# lyre_v1_1.net
KiCad netlist of a schematic drawn in EAGLE
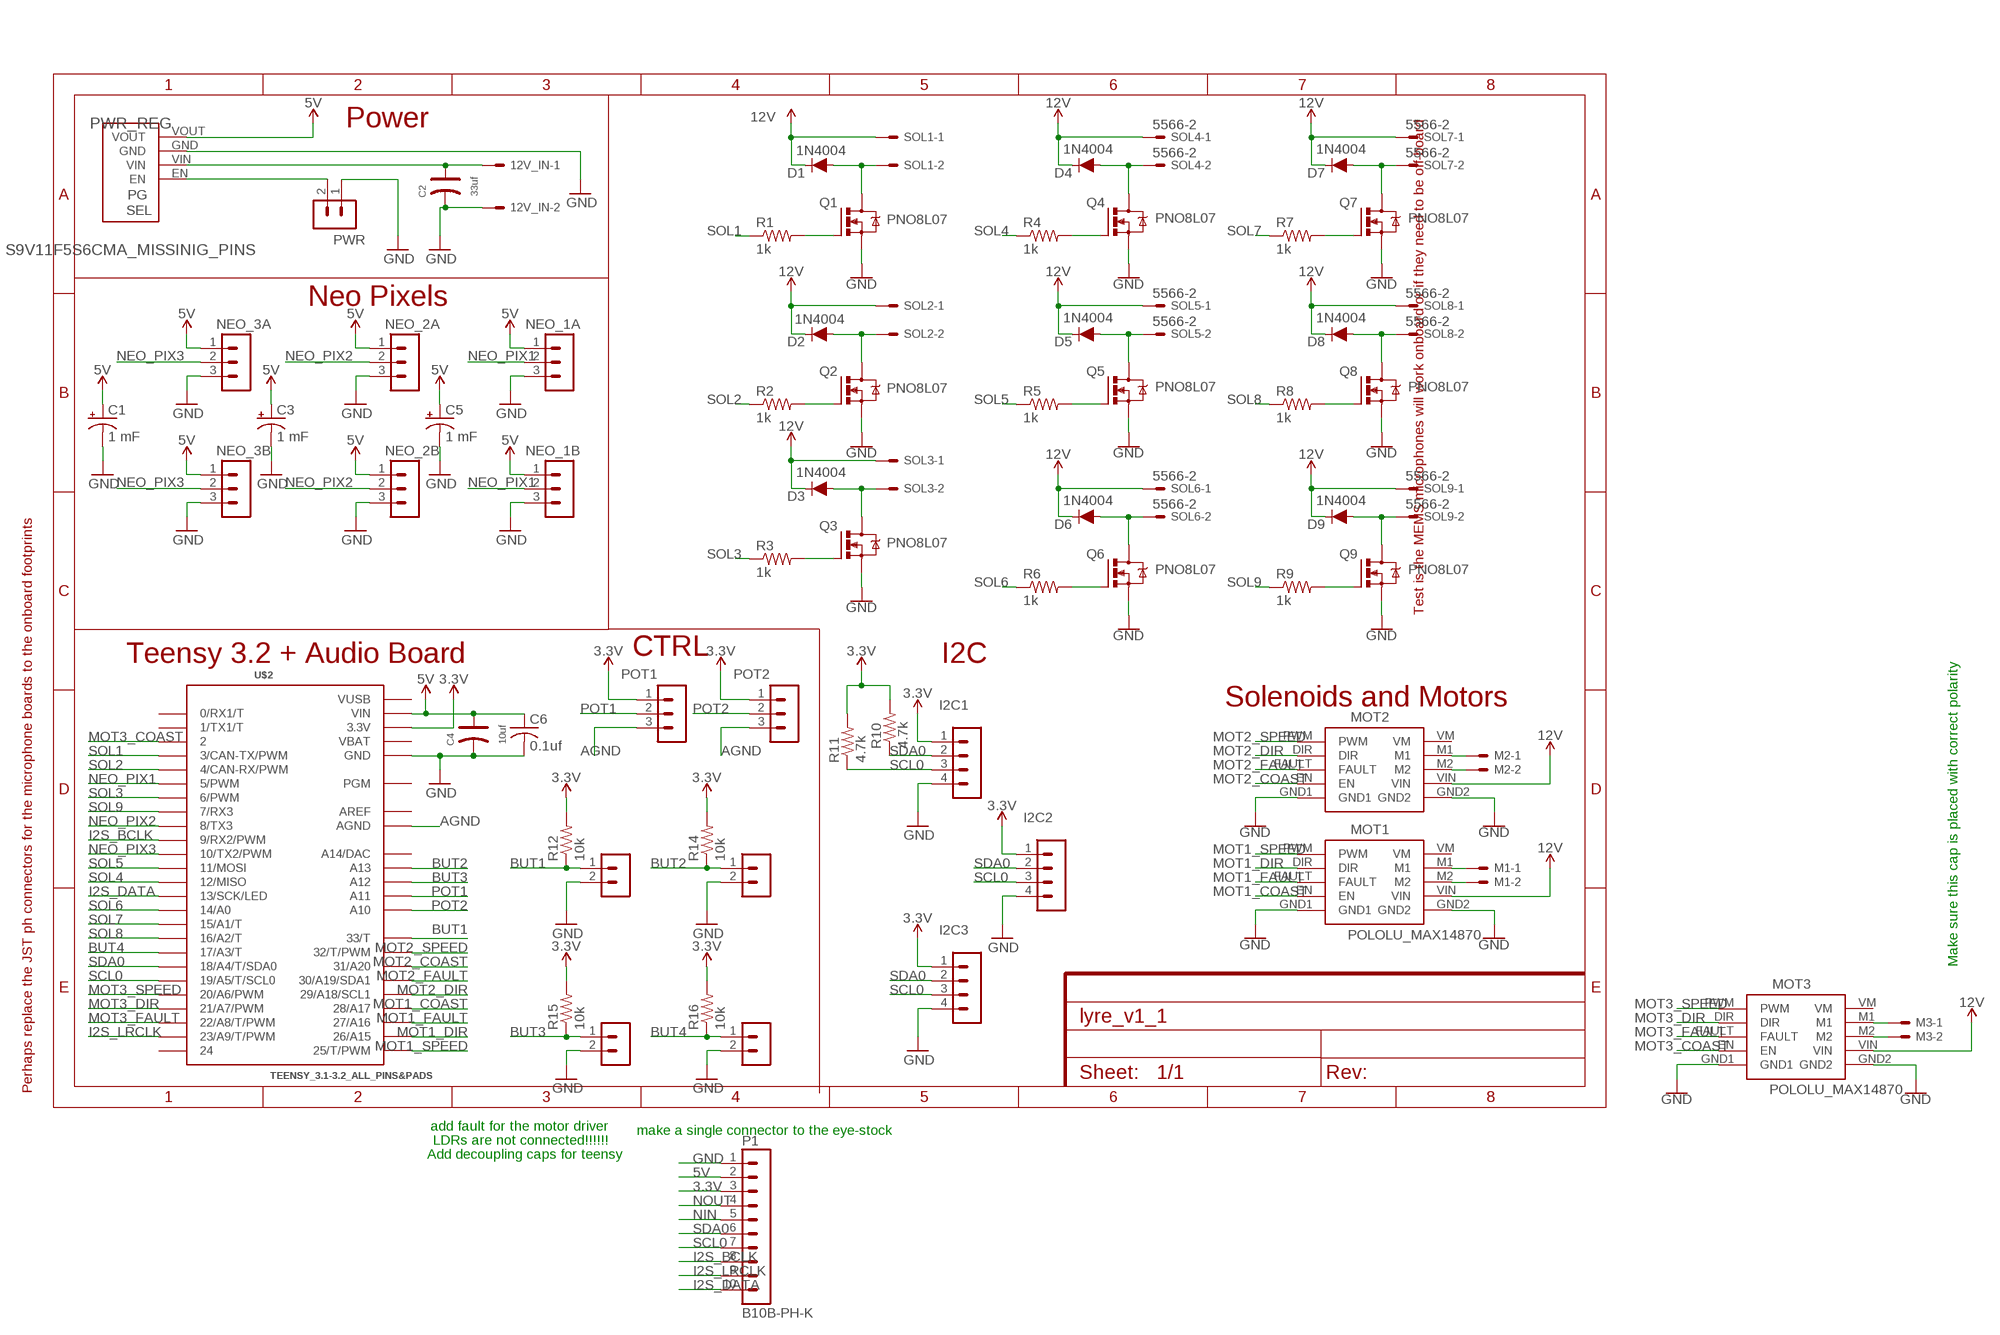
[diagram p0: schematic, sheet 1]

(export (version "E")
  (design (tool "Eeschema 10.0.6"))
  (components
    (comp (ref "12V_IN")
      (value "5566-2")
      (footprint "eagle-import:5566-2")
      (fields (field (name "MF") "MOLEX"))
      (libsource (lib "eagle-import") (part "5566-2"))
    )
    (comp (ref "BUT1")
      (value "B2B-PH-K")
      (footprint "eagle-import:B2B-PH-K")
      (libsource (lib "eagle-import") (part "B2B-PH-K"))
    )
    (comp (ref "BUT2")
      (value "B2B-PH-K")
      (footprint "eagle-import:B2B-PH-K")
      (libsource (lib "eagle-import") (part "B2B-PH-K"))
    )
    (comp (ref "BUT3")
      (value "B2B-PH-K")
      (footprint "eagle-import:B2B-PH-K")
      (libsource (lib "eagle-import") (part "B2B-PH-K"))
    )
    (comp (ref "BUT4")
      (value "B2B-PH-K")
      (footprint "eagle-import:B2B-PH-K")
      (libsource (lib "eagle-import") (part "B2B-PH-K"))
    )
    (comp (ref "C1")
      (value "1 mF")
      (footprint "eagle-import:UD-10X10_NICHICON")
      (libsource (lib "eagle-import") (part "CPOL-USUD-10X10"))
    )
    (comp (ref "C2")
      (value "33uf")
      (footprint "eagle-import:PC-D5.3MM")
      (fields (field (name "MPN") "KS 100uF/16V"))
      (libsource (lib "eagle-import") (part "DIP-ALUMINUM-47UF-16V(D5-H7MM)"))
    )
    (comp (ref "C3")
      (value "1 mF")
      (footprint "eagle-import:UD-10X10_NICHICON")
      (libsource (lib "eagle-import") (part "CPOL-USUD-10X10"))
    )
    (comp (ref "C4")
      (value "10uf")
      (footprint "eagle-import:PC-D5.3MM")
      (fields (field (name "MPN") "KS 100uF/16V"))
      (libsource (lib "eagle-import") (part "DIP-ALUMINUM-47UF-16V(D5-H7MM)"))
    )
    (comp (ref "C5")
      (value "1 mF")
      (footprint "eagle-import:UD-10X10_NICHICON")
      (libsource (lib "eagle-import") (part "CPOL-USUD-10X10"))
    )
    (comp (ref "C6")
      (value "0.1uf")
      (footprint "eagle-import:C2012")
      (libsource (lib "eagle-import") (part "C-USC2012"))
    )
    (comp (ref "D1")
      (value "1N4004")
      (footprint "eagle-import:DIOAD1138W86L465D235B")
      (libsource (lib "eagle-import") (part "1N4004"))
    )
    (comp (ref "D2")
      (value "1N4004")
      (footprint "eagle-import:DIOAD1138W86L465D235B")
      (libsource (lib "eagle-import") (part "1N4004"))
    )
    (comp (ref "D3")
      (value "1N4004")
      (footprint "eagle-import:DIOAD1138W86L465D235B")
      (libsource (lib "eagle-import") (part "1N4004"))
    )
    (comp (ref "D4")
      (value "1N4004")
      (footprint "eagle-import:DIOAD1138W86L465D235B")
      (libsource (lib "eagle-import") (part "1N4004"))
    )
    (comp (ref "D5")
      (value "1N4004")
      (footprint "eagle-import:DIOAD1138W86L465D235B")
      (libsource (lib "eagle-import") (part "1N4004"))
    )
    (comp (ref "D6")
      (value "1N4004")
      (footprint "eagle-import:DIOAD1138W86L465D235B")
      (libsource (lib "eagle-import") (part "1N4004"))
    )
    (comp (ref "D7")
      (value "1N4004")
      (footprint "eagle-import:DIOAD1138W86L465D235B")
      (libsource (lib "eagle-import") (part "1N4004"))
    )
    (comp (ref "D8")
      (value "1N4004")
      (footprint "eagle-import:DIOAD1138W86L465D235B")
      (libsource (lib "eagle-import") (part "1N4004"))
    )
    (comp (ref "D9")
      (value "1N4004")
      (footprint "eagle-import:DIOAD1138W86L465D235B")
      (libsource (lib "eagle-import") (part "1N4004"))
    )
    (comp (ref "I2C1")
      (value "B4B-PH-K")
      (footprint "eagle-import:B4B-PH-K")
      (libsource (lib "eagle-import") (part "B4B-PH-K"))
    )
    (comp (ref "I2C2")
      (value "B4B-PH-K")
      (footprint "eagle-import:B4B-PH-K")
      (libsource (lib "eagle-import") (part "B4B-PH-K"))
    )
    (comp (ref "I2C3")
      (value "B4B-PH-K")
      (footprint "eagle-import:B4B-PH-K")
      (libsource (lib "eagle-import") (part "B4B-PH-K"))
    )
    (comp (ref "M1")
      (value "5566-2")
      (footprint "eagle-import:5566-2")
      (fields (field (name "MF") "MOLEX"))
      (libsource (lib "eagle-import") (part "5566-2"))
    )
    (comp (ref "M2")
      (value "5566-2")
      (footprint "eagle-import:5566-2")
      (fields (field (name "MF") "MOLEX"))
      (libsource (lib "eagle-import") (part "5566-2"))
    )
    (comp (ref "M3")
      (value "5566-2")
      (footprint "eagle-import:5566-2")
      (fields (field (name "MF") "MOLEX"))
      (libsource (lib "eagle-import") (part "5566-2"))
    )
    (comp (ref "MOT1")
      (value "POLOLU_MAX14870")
      (footprint "eagle-import:POLOLU_MAX14870")
      (libsource (lib "eagle-import") (part "POLOLU_MAX14870"))
    )
    (comp (ref "MOT2")
      (value "POLOLU_MAX14870")
      (footprint "eagle-import:POLOLU_MAX14870")
      (libsource (lib "eagle-import") (part "POLOLU_MAX14870"))
    )
    (comp (ref "MOT3")
      (value "POLOLU_MAX14870")
      (footprint "eagle-import:POLOLU_MAX14870")
      (libsource (lib "eagle-import") (part "POLOLU_MAX14870"))
    )
    (comp (ref "NEO_1A")
      (value "B3B-PH-K")
      (footprint "eagle-import:B3B-PH-K")
      (libsource (lib "eagle-import") (part "B3B-PH-K"))
    )
    (comp (ref "NEO_1B")
      (value "B3B-PH-K")
      (footprint "eagle-import:B3B-PH-K")
      (libsource (lib "eagle-import") (part "B3B-PH-K"))
    )
    (comp (ref "NEO_2A")
      (value "B3B-PH-K")
      (footprint "eagle-import:B3B-PH-K")
      (libsource (lib "eagle-import") (part "B3B-PH-K"))
    )
    (comp (ref "NEO_2B")
      (value "B3B-PH-K")
      (footprint "eagle-import:B3B-PH-K")
      (libsource (lib "eagle-import") (part "B3B-PH-K"))
    )
    (comp (ref "NEO_3A")
      (value "B3B-PH-K")
      (footprint "eagle-import:B3B-PH-K")
      (libsource (lib "eagle-import") (part "B3B-PH-K"))
    )
    (comp (ref "NEO_3B")
      (value "B3B-PH-K")
      (footprint "eagle-import:B3B-PH-K")
      (libsource (lib "eagle-import") (part "B3B-PH-K"))
    )
    (comp (ref "P1")
      (value "B10B-PH-K")
      (footprint "eagle-import:B10B-PH-K")
      (libsource (lib "eagle-import") (part "B10B-PH-K"))
    )
    (comp (ref "POT1")
      (value "B3B-PH-K")
      (footprint "eagle-import:B3B-PH-K")
      (libsource (lib "eagle-import") (part "B3B-PH-K"))
    )
    (comp (ref "POT2")
      (value "B3B-PH-K")
      (footprint "eagle-import:B3B-PH-K")
      (libsource (lib "eagle-import") (part "B3B-PH-K"))
    )
    (comp (ref "PWR")
      (value "B2B-PH-K")
      (footprint "eagle-import:B2B-PH-K")
      (libsource (lib "eagle-import") (part "B2B-PH-K"))
    )
    (comp (ref "PWR_REG")
      (value "S9V11F5S6CMA_MISSINIG_PINS")
      (footprint "eagle-import:S9V11F3S5CMA_MISSING_PINS")
      (libsource (lib "eagle-import") (part "S9V11F5S6CMA_MISSINIG_PINS"))
    )
    (comp (ref "Q1")
      (value "PNO8L07")
      (footprint "eagle-import:TO220BV")
      (libsource (lib "eagle-import") (part "IRF540"))
    )
    (comp (ref "Q2")
      (value "PNO8L07")
      (footprint "eagle-import:TO220BV")
      (libsource (lib "eagle-import") (part "IRF540"))
    )
    (comp (ref "Q3")
      (value "PNO8L07")
      (footprint "eagle-import:TO220BV")
      (libsource (lib "eagle-import") (part "IRF540"))
    )
    (comp (ref "Q4")
      (value "PNO8L07")
      (footprint "eagle-import:TO220BV")
      (libsource (lib "eagle-import") (part "IRF540"))
    )
    (comp (ref "Q5")
      (value "PNO8L07")
      (footprint "eagle-import:TO220BV")
      (libsource (lib "eagle-import") (part "IRF540"))
    )
    (comp (ref "Q6")
      (value "PNO8L07")
      (footprint "eagle-import:TO220BV")
      (libsource (lib "eagle-import") (part "IRF540"))
    )
    (comp (ref "Q7")
      (value "PNO8L07")
      (footprint "eagle-import:TO220BV")
      (libsource (lib "eagle-import") (part "IRF540"))
    )
    (comp (ref "Q8")
      (value "PNO8L07")
      (footprint "eagle-import:TO220BV")
      (libsource (lib "eagle-import") (part "IRF540"))
    )
    (comp (ref "Q9")
      (value "PNO8L07")
      (footprint "eagle-import:TO220BV")
      (libsource (lib "eagle-import") (part "IRF540"))
    )
    (comp (ref "R1")
      (value "1k")
      (footprint "eagle-import:R0805")
      (libsource (lib "eagle-import") (part "R-US_R0805"))
    )
    (comp (ref "R2")
      (value "1k")
      (footprint "eagle-import:R0805")
      (libsource (lib "eagle-import") (part "R-US_R0805"))
    )
    (comp (ref "R3")
      (value "1k")
      (footprint "eagle-import:R0805")
      (libsource (lib "eagle-import") (part "R-US_R0805"))
    )
    (comp (ref "R4")
      (value "1k")
      (footprint "eagle-import:R0805")
      (libsource (lib "eagle-import") (part "R-US_R0805"))
    )
    (comp (ref "R5")
      (value "1k")
      (footprint "eagle-import:R0805")
      (libsource (lib "eagle-import") (part "R-US_R0805"))
    )
    (comp (ref "R6")
      (value "1k")
      (footprint "eagle-import:R0805")
      (libsource (lib "eagle-import") (part "R-US_R0805"))
    )
    (comp (ref "R7")
      (value "1k")
      (footprint "eagle-import:R0805")
      (libsource (lib "eagle-import") (part "R-US_R0805"))
    )
    (comp (ref "R8")
      (value "1k")
      (footprint "eagle-import:R0805")
      (libsource (lib "eagle-import") (part "R-US_R0805"))
    )
    (comp (ref "R9")
      (value "1k")
      (footprint "eagle-import:R0805")
      (libsource (lib "eagle-import") (part "R-US_R0805"))
    )
    (comp (ref "R10")
      (value "4.7k")
      (footprint "eagle-import:R0805")
      (libsource (lib "eagle-import") (part "R-US_R0805"))
    )
    (comp (ref "R11")
      (value "4.7k")
      (footprint "eagle-import:R0805")
      (libsource (lib "eagle-import") (part "R-US_R0805"))
    )
    (comp (ref "R12")
      (value "10k")
      (footprint "eagle-import:R0805")
      (libsource (lib "eagle-import") (part "R-US_R0805"))
    )
    (comp (ref "R14")
      (value "10k")
      (footprint "eagle-import:R0805")
      (libsource (lib "eagle-import") (part "R-US_R0805"))
    )
    (comp (ref "R15")
      (value "10k")
      (footprint "eagle-import:R0805")
      (libsource (lib "eagle-import") (part "R-US_R0805"))
    )
    (comp (ref "R16")
      (value "10k")
      (footprint "eagle-import:R0805")
      (libsource (lib "eagle-import") (part "R-US_R0805"))
    )
    (comp (ref "SOL1")
      (value "5566-2")
      (footprint "eagle-import:5566-2")
      (fields (field (name "MF") "MOLEX"))
      (libsource (lib "eagle-import") (part "5566-2"))
    )
    (comp (ref "SOL2")
      (value "5566-2")
      (footprint "eagle-import:5566-2")
      (fields (field (name "MF") "MOLEX"))
      (libsource (lib "eagle-import") (part "5566-2"))
    )
    (comp (ref "SOL3")
      (value "5566-2")
      (footprint "eagle-import:5566-2")
      (fields (field (name "MF") "MOLEX"))
      (libsource (lib "eagle-import") (part "5566-2"))
    )
    (comp (ref "SOL4")
      (value "5566-2")
      (footprint "eagle-import:5566-2")
      (fields (field (name "MF") "MOLEX"))
      (libsource (lib "eagle-import") (part "5566-2"))
    )
    (comp (ref "SOL5")
      (value "5566-2")
      (footprint "eagle-import:5566-2")
      (fields (field (name "MF") "MOLEX"))
      (libsource (lib "eagle-import") (part "5566-2"))
    )
    (comp (ref "SOL6")
      (value "5566-2")
      (footprint "eagle-import:5566-2")
      (fields (field (name "MF") "MOLEX"))
      (libsource (lib "eagle-import") (part "5566-2"))
    )
    (comp (ref "SOL7")
      (value "5566-2")
      (footprint "eagle-import:5566-2")
      (fields (field (name "MF") "MOLEX"))
      (libsource (lib "eagle-import") (part "5566-2"))
    )
    (comp (ref "SOL8")
      (value "5566-2")
      (footprint "eagle-import:5566-2")
      (fields (field (name "MF") "MOLEX"))
      (libsource (lib "eagle-import") (part "5566-2"))
    )
    (comp (ref "SOL9")
      (value "5566-2")
      (footprint "eagle-import:5566-2")
      (fields (field (name "MF") "MOLEX"))
      (libsource (lib "eagle-import") (part "5566-2"))
    )
    (comp (ref "U$2")
      (value "TEENSY_3.1-3.2_ALL_PINS&PADS")
      (footprint "eagle-import:TEENSY_3.0-3.2_ALL_PINS_&_PADS")
      (libsource (lib "eagle-import") (part "TEENSY_3.1-3.2_ALL_PINS&PADS"))
    )
  )
  (nets
    (net (code "1") (name "/AGND") (class "Default")
      (node (ref "POT1") (pin "3") (pinfunction "3_3") (pintype "passive"))
      (node (ref "POT2") (pin "3") (pinfunction "3_3") (pintype "passive"))
      (node (ref "U$2") (pin "AGND") (pinfunction "AGND_AGND") (pintype "power_in"))
    )
    (net (code "2") (name "/AREF") (class "Default")
      (node (ref "U$2") (pin "AREF") (pinfunction "AREF_AREF") (pintype "power_in"))
    )
    (net (code "3") (name "/BUT1") (class "Default")
      (node (ref "BUT1") (pin "1") (pinfunction "1_1") (pintype "passive"))
      (node (ref "R12") (pin "1") (pinfunction "1_1") (pintype "passive"))
      (node (ref "U$2") (pin "33") (pinfunction "33/T_33") (pintype "bidirectional"))
    )
    (net (code "4") (name "/BUT2") (class "Default")
      (node (ref "BUT2") (pin "1") (pinfunction "1_1") (pintype "passive"))
      (node (ref "R14") (pin "1") (pinfunction "1_1") (pintype "passive"))
      (node (ref "U$2") (pin "A13") (pinfunction "A13_A13") (pintype "bidirectional"))
    )
    (net (code "5") (name "/BUT3") (class "Default")
      (node (ref "BUT3") (pin "1") (pinfunction "1_1") (pintype "passive"))
      (node (ref "R15") (pin "1") (pinfunction "1_1") (pintype "passive"))
      (node (ref "U$2") (pin "A12") (pinfunction "A12_A12") (pintype "bidirectional"))
    )
    (net (code "6") (name "/BUT4") (class "Default")
      (node (ref "BUT4") (pin "1") (pinfunction "1_1") (pintype "passive"))
      (node (ref "R16") (pin "1") (pinfunction "1_1") (pintype "passive"))
      (node (ref "U$2") (pin "17/A3") (pinfunction "17/A3/T_17/A3") (pintype "bidirectional"))
    )
    (net (code "7") (name "/I2S_BCLK") (class "Default")
      (node (ref "P1") (pin "8") (pinfunction "8_8") (pintype "passive"))
      (node (ref "U$2") (pin "9") (pinfunction "9/RX2/PWM_9") (pintype "bidirectional"))
    )
    (net (code "8") (name "/I2S_DATA") (class "Default")
      (node (ref "P1") (pin "10") (pinfunction "10_10") (pintype "passive"))
      (node (ref "U$2") (pin "13") (pinfunction "13/SCK/LED_13") (pintype "bidirectional"))
    )
    (net (code "9") (name "/I2S_LRCLK") (class "Default")
      (node (ref "P1") (pin "9") (pinfunction "9_9") (pintype "passive"))
      (node (ref "U$2") (pin "23/A9") (pinfunction "23/A9/T/PWM_23/A9") (pintype "bidirectional"))
    )
    (net (code "10") (name "/MOT1_COAST") (class "Default")
      (node (ref "MOT1") (pin "EN") (pinfunction "EN_EN") (pintype "bidirectional"))
      (node (ref "U$2") (pin "28") (pinfunction "28/A17_28") (pintype "bidirectional"))
    )
    (net (code "11") (name "/MOT1_DIR") (class "Default")
      (node (ref "MOT1") (pin "DIR") (pinfunction "DIR_DIR") (pintype "bidirectional"))
      (node (ref "U$2") (pin "26") (pinfunction "26/A15_26") (pintype "bidirectional"))
    )
    (net (code "12") (name "/MOT1_FAULT") (class "Default")
      (node (ref "MOT1") (pin "FAULT") (pinfunction "FAULT_FAULT") (pintype "bidirectional"))
      (node (ref "U$2") (pin "27") (pinfunction "27/A16_27") (pintype "bidirectional"))
    )
    (net (code "13") (name "/MOT1_SPEED") (class "Default")
      (node (ref "MOT1") (pin "PWM") (pinfunction "PWM_PWM") (pintype "bidirectional"))
      (node (ref "U$2") (pin "25") (pinfunction "25/T/PWM_25") (pintype "bidirectional"))
    )
    (net (code "14") (name "/MOT2_COAST") (class "Default")
      (node (ref "MOT2") (pin "EN") (pinfunction "EN_EN") (pintype "bidirectional"))
      (node (ref "U$2") (pin "31") (pinfunction "31/A20_31") (pintype "bidirectional"))
    )
    (net (code "15") (name "/MOT2_DIR") (class "Default")
      (node (ref "MOT2") (pin "DIR") (pinfunction "DIR_DIR") (pintype "bidirectional"))
      (node (ref "U$2") (pin "29") (pinfunction "29/A18/SCL1_29") (pintype "bidirectional"))
    )
    (net (code "16") (name "/MOT2_FAULT") (class "Default")
      (node (ref "MOT2") (pin "FAULT") (pinfunction "FAULT_FAULT") (pintype "bidirectional"))
      (node (ref "U$2") (pin "30") (pinfunction "30/A19/SDA1_30") (pintype "bidirectional"))
    )
    (net (code "17") (name "/MOT2_SPEED") (class "Default")
      (node (ref "MOT2") (pin "PWM") (pinfunction "PWM_PWM") (pintype "bidirectional"))
      (node (ref "U$2") (pin "32") (pinfunction "32/T/PWM_32") (pintype "bidirectional"))
    )
    (net (code "18") (name "/MOT3_COAST") (class "Default")
      (node (ref "MOT3") (pin "EN") (pinfunction "EN_EN") (pintype "bidirectional"))
      (node (ref "U$2") (pin "2") (pinfunction "2_2") (pintype "bidirectional"))
    )
    (net (code "19") (name "/MOT3_DIR") (class "Default")
      (node (ref "MOT3") (pin "DIR") (pinfunction "DIR_DIR") (pintype "bidirectional"))
      (node (ref "U$2") (pin "21/A7") (pinfunction "21/A7/PWM_21/A7") (pintype "bidirectional"))
    )
    (net (code "20") (name "/MOT3_FAULT") (class "Default")
      (node (ref "MOT3") (pin "FAULT") (pinfunction "FAULT_FAULT") (pintype "bidirectional"))
      (node (ref "U$2") (pin "22/A8") (pinfunction "22/A8/T/PWM_22/A8") (pintype "bidirectional"))
    )
    (net (code "21") (name "/MOT3_SPEED") (class "Default")
      (node (ref "MOT3") (pin "PWM") (pinfunction "PWM_PWM") (pintype "bidirectional"))
      (node (ref "U$2") (pin "20/A6") (pinfunction "20/A6/PWM_20/A6") (pintype "bidirectional"))
    )
    (net (code "22") (name "/NEO_PIX1") (class "Default")
      (node (ref "NEO_1A") (pin "2") (pinfunction "2_2") (pintype "passive"))
      (node (ref "NEO_1B") (pin "2") (pinfunction "2_2") (pintype "passive"))
      (node (ref "U$2") (pin "5") (pinfunction "5/PWM_5") (pintype "bidirectional"))
    )
    (net (code "23") (name "/NEO_PIX2") (class "Default")
      (node (ref "NEO_2A") (pin "2") (pinfunction "2_2") (pintype "passive"))
      (node (ref "NEO_2B") (pin "2") (pinfunction "2_2") (pintype "passive"))
      (node (ref "U$2") (pin "8") (pinfunction "8/TX3_8") (pintype "bidirectional"))
    )
    (net (code "24") (name "/NEO_PIX3") (class "Default")
      (node (ref "NEO_3A") (pin "2") (pinfunction "2_2") (pintype "passive"))
      (node (ref "NEO_3B") (pin "2") (pinfunction "2_2") (pintype "passive"))
      (node (ref "U$2") (pin "10") (pinfunction "10/TX2/PWM_10") (pintype "bidirectional"))
    )
    (net (code "25") (name "/NIN") (class "Default")
      (node (ref "P1") (pin "5") (pinfunction "5_5") (pintype "passive"))
    )
    (net (code "26") (name "/NOUT") (class "Default")
      (node (ref "P1") (pin "4") (pinfunction "4_4") (pintype "passive"))
    )
    (net (code "27") (name "/POT1") (class "Default")
      (node (ref "POT1") (pin "2") (pinfunction "2_2") (pintype "passive"))
      (node (ref "U$2") (pin "A11") (pinfunction "A11_A11") (pintype "bidirectional"))
    )
    (net (code "28") (name "/POT2") (class "Default")
      (node (ref "POT2") (pin "2") (pinfunction "2_2") (pintype "passive"))
      (node (ref "U$2") (pin "A10") (pinfunction "A10_A10") (pintype "bidirectional"))
    )
    (net (code "29") (name "/SCL0") (class "Default")
      (node (ref "I2C1") (pin "3") (pinfunction "3_3") (pintype "passive"))
      (node (ref "I2C2") (pin "3") (pinfunction "3_3") (pintype "passive"))
      (node (ref "I2C3") (pin "3") (pinfunction "3_3") (pintype "passive"))
      (node (ref "P1") (pin "7") (pinfunction "7_7") (pintype "passive"))
      (node (ref "R11") (pin "1") (pinfunction "1_1") (pintype "passive"))
      (node (ref "U$2") (pin "19/A5") (pinfunction "19/A5/T/SCL0_19/A5") (pintype "bidirectional"))
    )
    (net (code "30") (name "/SDA0") (class "Default")
      (node (ref "I2C1") (pin "2") (pinfunction "2_2") (pintype "passive"))
      (node (ref "I2C2") (pin "2") (pinfunction "2_2") (pintype "passive"))
      (node (ref "I2C3") (pin "2") (pinfunction "2_2") (pintype "passive"))
      (node (ref "P1") (pin "6") (pinfunction "6_6") (pintype "passive"))
      (node (ref "R10") (pin "1") (pinfunction "1_1") (pintype "passive"))
      (node (ref "U$2") (pin "18/A4") (pinfunction "18/A4/T/SDA0_18/A4") (pintype "bidirectional"))
    )
    (net (code "31") (name "/SOL1") (class "Default")
      (node (ref "R1") (pin "1") (pinfunction "1_1") (pintype "passive"))
      (node (ref "U$2") (pin "3") (pinfunction "3/CAN-TX/PWM_3") (pintype "bidirectional"))
    )
    (net (code "32") (name "/SOL2") (class "Default")
      (node (ref "R2") (pin "1") (pinfunction "1_1") (pintype "passive"))
      (node (ref "U$2") (pin "4") (pinfunction "4/CAN-RX/PWM_4") (pintype "bidirectional"))
    )
    (net (code "33") (name "/SOL3") (class "Default")
      (node (ref "R3") (pin "1") (pinfunction "1_1") (pintype "passive"))
      (node (ref "U$2") (pin "6") (pinfunction "6/PWM_6") (pintype "bidirectional"))
    )
    (net (code "34") (name "/SOL4") (class "Default")
      (node (ref "R4") (pin "1") (pinfunction "1_1") (pintype "passive"))
      (node (ref "U$2") (pin "12") (pinfunction "12/MISO_12") (pintype "bidirectional"))
    )
    (net (code "35") (name "/SOL5") (class "Default")
      (node (ref "R5") (pin "1") (pinfunction "1_1") (pintype "passive"))
      (node (ref "U$2") (pin "11") (pinfunction "11/MOSI_11") (pintype "bidirectional"))
    )
    (net (code "36") (name "/SOL6") (class "Default")
      (node (ref "R6") (pin "1") (pinfunction "1_1") (pintype "passive"))
      (node (ref "U$2") (pin "14/A0") (pinfunction "14/A0_14/A0") (pintype "bidirectional"))
    )
    (net (code "37") (name "/SOL7") (class "Default")
      (node (ref "R7") (pin "1") (pinfunction "1_1") (pintype "passive"))
      (node (ref "U$2") (pin "15/A1") (pinfunction "15/A1/T_15/A1") (pintype "bidirectional"))
    )
    (net (code "38") (name "/SOL8") (class "Default")
      (node (ref "R8") (pin "1") (pinfunction "1_1") (pintype "passive"))
      (node (ref "U$2") (pin "16/A2") (pinfunction "16/A2/T_16/A2") (pintype "bidirectional"))
    )
    (net (code "39") (name "/SOL9") (class "Default")
      (node (ref "R9") (pin "1") (pinfunction "1_1") (pintype "passive"))
      (node (ref "U$2") (pin "7") (pinfunction "7/RX3_7") (pintype "bidirectional"))
    )
    (net (code "40") (name "/VBAT") (class "Default")
      (node (ref "U$2") (pin "VBAT") (pinfunction "VBAT_VBAT") (pintype "power_in"))
    )
    (net (code "41") (name "/VUSB") (class "Default")
      (node (ref "U$2") (pin "VUSB") (pinfunction "VUSB_VUSB") (pintype "power_in"))
    )
    (net (code "42") (name "3.3V") (class "Default")
      (node (ref "I2C1") (pin "1") (pinfunction "1_1") (pintype "passive"))
      (node (ref "I2C2") (pin "1") (pinfunction "1_1") (pintype "passive"))
      (node (ref "I2C3") (pin "1") (pinfunction "1_1") (pintype "passive"))
      (node (ref "P1") (pin "3") (pinfunction "3_3") (pintype "passive"))
      (node (ref "POT1") (pin "1") (pinfunction "1_1") (pintype "passive"))
      (node (ref "POT2") (pin "1") (pinfunction "1_1") (pintype "passive"))
      (node (ref "R10") (pin "2") (pinfunction "2_2") (pintype "passive"))
      (node (ref "R11") (pin "2") (pinfunction "2_2") (pintype "passive"))
      (node (ref "R12") (pin "2") (pinfunction "2_2") (pintype "passive"))
      (node (ref "R14") (pin "2") (pinfunction "2_2") (pintype "passive"))
      (node (ref "R15") (pin "2") (pinfunction "2_2") (pintype "passive"))
      (node (ref "R16") (pin "2") (pinfunction "2_2") (pintype "passive"))
      (node (ref "U$2") (pin "3.3V") (pinfunction "3.3V_3.3V") (pintype "power_in"))
      (node (ref "U$2") (pin "3.3V1") (pinfunction "3.3V_3.3V1") (pintype "power_in"))
      (node (ref "U$2") (pin "3.3V2") (pinfunction "3.3V_3.3V2") (pintype "power_in"))
    )
    (net (code "43") (name "5V") (class "Default")
      (node (ref "C1") (pin "+") (pinfunction "+_+") (pintype "passive"))
      (node (ref "C3") (pin "+") (pinfunction "+_+") (pintype "passive"))
      (node (ref "C4") (pin "+") (pinfunction "+_+") (pintype "passive"))
      (node (ref "C5") (pin "+") (pinfunction "+_+") (pintype "passive"))
      (node (ref "C6") (pin "1") (pinfunction "1_1") (pintype "passive"))
      (node (ref "NEO_1A") (pin "1") (pinfunction "1_1") (pintype "passive"))
      (node (ref "NEO_1B") (pin "1") (pinfunction "1_1") (pintype "passive"))
      (node (ref "NEO_2A") (pin "1") (pinfunction "1_1") (pintype "passive"))
      (node (ref "NEO_2B") (pin "1") (pinfunction "1_1") (pintype "passive"))
      (node (ref "NEO_3A") (pin "1") (pinfunction "1_1") (pintype "passive"))
      (node (ref "NEO_3B") (pin "1") (pinfunction "1_1") (pintype "passive"))
      (node (ref "P1") (pin "2") (pinfunction "2_2") (pintype "passive"))
      (node (ref "PWR_REG") (pin "VOUT") (pinfunction "VOUT_VOUT") (pintype "bidirectional"))
      (node (ref "U$2") (pin "VIN") (pinfunction "VIN_VIN") (pintype "power_in"))
    )
    (net (code "44") (name "12V") (class "Default")
      (node (ref "12V_IN") (pin "1") (pinfunction "S_1") (pintype "passive"))
      (node (ref "C2") (pin "+") (pinfunction "+_+") (pintype "passive"))
      (node (ref "D1") (pin "2") (pinfunction "C_2") (pintype "passive"))
      (node (ref "D2") (pin "2") (pinfunction "C_2") (pintype "passive"))
      (node (ref "D3") (pin "2") (pinfunction "C_2") (pintype "passive"))
      (node (ref "D4") (pin "2") (pinfunction "C_2") (pintype "passive"))
      (node (ref "D5") (pin "2") (pinfunction "C_2") (pintype "passive"))
      (node (ref "D6") (pin "2") (pinfunction "C_2") (pintype "passive"))
      (node (ref "D7") (pin "2") (pinfunction "C_2") (pintype "passive"))
      (node (ref "D8") (pin "2") (pinfunction "C_2") (pintype "passive"))
      (node (ref "D9") (pin "2") (pinfunction "C_2") (pintype "passive"))
      (node (ref "MOT1") (pin "VIN") (pinfunction "VIN_VIN") (pintype "bidirectional"))
      (node (ref "MOT2") (pin "VIN") (pinfunction "VIN_VIN") (pintype "bidirectional"))
      (node (ref "MOT3") (pin "VIN") (pinfunction "VIN_VIN") (pintype "bidirectional"))
      (node (ref "PWR_REG") (pin "VIN") (pinfunction "VIN_VIN") (pintype "bidirectional"))
      (node (ref "SOL1") (pin "1") (pinfunction "S_1") (pintype "passive"))
      (node (ref "SOL2") (pin "1") (pinfunction "S_1") (pintype "passive"))
      (node (ref "SOL3") (pin "1") (pinfunction "S_1") (pintype "passive"))
      (node (ref "SOL4") (pin "1") (pinfunction "S_1") (pintype "passive"))
      (node (ref "SOL5") (pin "1") (pinfunction "S_1") (pintype "passive"))
      (node (ref "SOL6") (pin "1") (pinfunction "S_1") (pintype "passive"))
      (node (ref "SOL7") (pin "1") (pinfunction "S_1") (pintype "passive"))
      (node (ref "SOL8") (pin "1") (pinfunction "S_1") (pintype "passive"))
      (node (ref "SOL9") (pin "1") (pinfunction "S_1") (pintype "passive"))
    )
    (net (code "45") (name "GND") (class "Default")
      (node (ref "12V_IN") (pin "2") (pinfunction "S_2") (pintype "passive"))
      (node (ref "BUT1") (pin "2") (pinfunction "2_2") (pintype "passive"))
      (node (ref "BUT2") (pin "2") (pinfunction "2_2") (pintype "passive"))
      (node (ref "BUT3") (pin "2") (pinfunction "2_2") (pintype "passive"))
      (node (ref "BUT4") (pin "2") (pinfunction "2_2") (pintype "passive"))
      (node (ref "C1") (pin "-") (pinfunction "-_-") (pintype "passive"))
      (node (ref "C2") (pin "-") (pinfunction "-_-") (pintype "passive"))
      (node (ref "C3") (pin "-") (pinfunction "-_-") (pintype "passive"))
      (node (ref "C4") (pin "-") (pinfunction "-_-") (pintype "passive"))
      (node (ref "C5") (pin "-") (pinfunction "-_-") (pintype "passive"))
      (node (ref "C6") (pin "2") (pinfunction "2_2") (pintype "passive"))
      (node (ref "I2C1") (pin "4") (pinfunction "4_4") (pintype "passive"))
      (node (ref "I2C2") (pin "4") (pinfunction "4_4") (pintype "passive"))
      (node (ref "I2C3") (pin "4") (pinfunction "4_4") (pintype "passive"))
      (node (ref "MOT1") (pin "GND1") (pinfunction "GND1_GND1") (pintype "bidirectional"))
      (node (ref "MOT1") (pin "GND2") (pinfunction "GND2_GND2") (pintype "bidirectional"))
      (node (ref "MOT2") (pin "GND1") (pinfunction "GND1_GND1") (pintype "bidirectional"))
      (node (ref "MOT2") (pin "GND2") (pinfunction "GND2_GND2") (pintype "bidirectional"))
      (node (ref "MOT3") (pin "GND1") (pinfunction "GND1_GND1") (pintype "bidirectional"))
      (node (ref "MOT3") (pin "GND2") (pinfunction "GND2_GND2") (pintype "bidirectional"))
      (node (ref "NEO_1A") (pin "3") (pinfunction "3_3") (pintype "passive"))
      (node (ref "NEO_1B") (pin "3") (pinfunction "3_3") (pintype "passive"))
      (node (ref "NEO_2A") (pin "3") (pinfunction "3_3") (pintype "passive"))
      (node (ref "NEO_2B") (pin "3") (pinfunction "3_3") (pintype "passive"))
      (node (ref "NEO_3A") (pin "3") (pinfunction "3_3") (pintype "passive"))
      (node (ref "NEO_3B") (pin "3") (pinfunction "3_3") (pintype "passive"))
      (node (ref "P1") (pin "1") (pinfunction "1_1") (pintype "passive"))
      (node (ref "PWR") (pin "1") (pinfunction "1_1") (pintype "passive"))
      (node (ref "PWR_REG") (pin "GND") (pinfunction "GND_GND") (pintype "bidirectional"))
      (node (ref "Q1") (pin "S") (pinfunction "S_S") (pintype "passive"))
      (node (ref "Q2") (pin "S") (pinfunction "S_S") (pintype "passive"))
      (node (ref "Q3") (pin "S") (pinfunction "S_S") (pintype "passive"))
      (node (ref "Q4") (pin "S") (pinfunction "S_S") (pintype "passive"))
      (node (ref "Q5") (pin "S") (pinfunction "S_S") (pintype "passive"))
      (node (ref "Q6") (pin "S") (pinfunction "S_S") (pintype "passive"))
      (node (ref "Q7") (pin "S") (pinfunction "S_S") (pintype "passive"))
      (node (ref "Q8") (pin "S") (pinfunction "S_S") (pintype "passive"))
      (node (ref "Q9") (pin "S") (pinfunction "S_S") (pintype "passive"))
      (node (ref "U$2") (pin "GND") (pinfunction "GND_GND") (pintype "power_in"))
      (node (ref "U$2") (pin "GND1") (pinfunction "GND_GND1") (pintype "power_in"))
      (node (ref "U$2") (pin "GND2") (pinfunction "GND_GND2") (pintype "power_in"))
    )
    (net (code "46") (name "Net-(D1-A)") (class "Default")
      (node (ref "D1") (pin "1") (pinfunction "A_1") (pintype "passive"))
      (node (ref "Q1") (pin "D") (pinfunction "D_D") (pintype "passive"))
      (node (ref "SOL1") (pin "2") (pinfunction "S_2") (pintype "passive"))
    )
    (net (code "47") (name "Net-(D2-A)") (class "Default")
      (node (ref "D2") (pin "1") (pinfunction "A_1") (pintype "passive"))
      (node (ref "Q2") (pin "D") (pinfunction "D_D") (pintype "passive"))
      (node (ref "SOL2") (pin "2") (pinfunction "S_2") (pintype "passive"))
    )
    (net (code "48") (name "Net-(D3-A)") (class "Default")
      (node (ref "D3") (pin "1") (pinfunction "A_1") (pintype "passive"))
      (node (ref "Q3") (pin "D") (pinfunction "D_D") (pintype "passive"))
      (node (ref "SOL3") (pin "2") (pinfunction "S_2") (pintype "passive"))
    )
    (net (code "49") (name "Net-(D4-A)") (class "Default")
      (node (ref "D4") (pin "1") (pinfunction "A_1") (pintype "passive"))
      (node (ref "Q4") (pin "D") (pinfunction "D_D") (pintype "passive"))
      (node (ref "SOL4") (pin "2") (pinfunction "S_2") (pintype "passive"))
    )
    (net (code "50") (name "Net-(D5-A)") (class "Default")
      (node (ref "D5") (pin "1") (pinfunction "A_1") (pintype "passive"))
      (node (ref "Q5") (pin "D") (pinfunction "D_D") (pintype "passive"))
      (node (ref "SOL5") (pin "2") (pinfunction "S_2") (pintype "passive"))
    )
    (net (code "51") (name "Net-(D6-A)") (class "Default")
      (node (ref "D6") (pin "1") (pinfunction "A_1") (pintype "passive"))
      (node (ref "Q6") (pin "D") (pinfunction "D_D") (pintype "passive"))
      (node (ref "SOL6") (pin "2") (pinfunction "S_2") (pintype "passive"))
    )
    (net (code "52") (name "Net-(D7-A)") (class "Default")
      (node (ref "D7") (pin "1") (pinfunction "A_1") (pintype "passive"))
      (node (ref "Q7") (pin "D") (pinfunction "D_D") (pintype "passive"))
      (node (ref "SOL7") (pin "2") (pinfunction "S_2") (pintype "passive"))
    )
    (net (code "53") (name "Net-(D8-A)") (class "Default")
      (node (ref "D8") (pin "1") (pinfunction "A_1") (pintype "passive"))
      (node (ref "Q8") (pin "D") (pinfunction "D_D") (pintype "passive"))
      (node (ref "SOL8") (pin "2") (pinfunction "S_2") (pintype "passive"))
    )
    (net (code "54") (name "Net-(D9-A)") (class "Default")
      (node (ref "D9") (pin "1") (pinfunction "A_1") (pintype "passive"))
      (node (ref "Q9") (pin "D") (pinfunction "D_D") (pintype "passive"))
      (node (ref "SOL9") (pin "2") (pinfunction "S_2") (pintype "passive"))
    )
    (net (code "55") (name "Net-(M1A-S)") (class "Default")
      (node (ref "M1") (pin "1") (pinfunction "S_1") (pintype "passive"))
      (node (ref "MOT1") (pin "M1") (pinfunction "M1_M1") (pintype "bidirectional"))
    )
    (net (code "56") (name "Net-(M1B-S)") (class "Default")
      (node (ref "M1") (pin "2") (pinfunction "S_2") (pintype "passive"))
      (node (ref "MOT1") (pin "M2") (pinfunction "M2_M2") (pintype "bidirectional"))
    )
    (net (code "57") (name "Net-(M2A-S)") (class "Default")
      (node (ref "M2") (pin "1") (pinfunction "S_1") (pintype "passive"))
      (node (ref "MOT2") (pin "M1") (pinfunction "M1_M1") (pintype "bidirectional"))
    )
    (net (code "58") (name "Net-(M2B-S)") (class "Default")
      (node (ref "M2") (pin "2") (pinfunction "S_2") (pintype "passive"))
      (node (ref "MOT2") (pin "M2") (pinfunction "M2_M2") (pintype "bidirectional"))
    )
    (net (code "59") (name "Net-(M3A-S)") (class "Default")
      (node (ref "M3") (pin "1") (pinfunction "S_1") (pintype "passive"))
      (node (ref "MOT3") (pin "M1") (pinfunction "M1_M1") (pintype "bidirectional"))
    )
    (net (code "60") (name "Net-(M3B-S)") (class "Default")
      (node (ref "M3") (pin "2") (pinfunction "S_2") (pintype "passive"))
      (node (ref "MOT3") (pin "M2") (pinfunction "M2_M2") (pintype "bidirectional"))
    )
    (net (code "61") (name "Net-(PWR-Pad2)") (class "Default")
      (node (ref "PWR") (pin "2") (pinfunction "2_2") (pintype "passive"))
      (node (ref "PWR_REG") (pin "EN") (pinfunction "EN_EN") (pintype "bidirectional"))
    )
    (net (code "62") (name "Net-(Q1-PadG)") (class "Default")
      (node (ref "Q1") (pin "G") (pinfunction "G_G") (pintype "passive"))
      (node (ref "R1") (pin "2") (pinfunction "2_2") (pintype "passive"))
    )
    (net (code "63") (name "Net-(Q2-PadG)") (class "Default")
      (node (ref "Q2") (pin "G") (pinfunction "G_G") (pintype "passive"))
      (node (ref "R2") (pin "2") (pinfunction "2_2") (pintype "passive"))
    )
    (net (code "64") (name "Net-(Q3-PadG)") (class "Default")
      (node (ref "Q3") (pin "G") (pinfunction "G_G") (pintype "passive"))
      (node (ref "R3") (pin "2") (pinfunction "2_2") (pintype "passive"))
    )
    (net (code "65") (name "Net-(Q4-PadG)") (class "Default")
      (node (ref "Q4") (pin "G") (pinfunction "G_G") (pintype "passive"))
      (node (ref "R4") (pin "2") (pinfunction "2_2") (pintype "passive"))
    )
    (net (code "66") (name "Net-(Q5-PadG)") (class "Default")
      (node (ref "Q5") (pin "G") (pinfunction "G_G") (pintype "passive"))
      (node (ref "R5") (pin "2") (pinfunction "2_2") (pintype "passive"))
    )
    (net (code "67") (name "Net-(Q6-PadG)") (class "Default")
      (node (ref "Q6") (pin "G") (pinfunction "G_G") (pintype "passive"))
      (node (ref "R6") (pin "2") (pinfunction "2_2") (pintype "passive"))
    )
    (net (code "68") (name "Net-(Q7-PadG)") (class "Default")
      (node (ref "Q7") (pin "G") (pinfunction "G_G") (pintype "passive"))
      (node (ref "R7") (pin "2") (pinfunction "2_2") (pintype "passive"))
    )
    (net (code "69") (name "Net-(Q8-PadG)") (class "Default")
      (node (ref "Q8") (pin "G") (pinfunction "G_G") (pintype "passive"))
      (node (ref "R8") (pin "2") (pinfunction "2_2") (pintype "passive"))
    )
    (net (code "70") (name "Net-(Q9-PadG)") (class "Default")
      (node (ref "Q9") (pin "G") (pinfunction "G_G") (pintype "passive"))
      (node (ref "R9") (pin "2") (pinfunction "2_2") (pintype "passive"))
    )
    (net (code "71") (name "unconnected-(MOT1-PadVM)") (class "Default")
      (node (ref "MOT1") (pin "VM") (pinfunction "VM_VM") (pintype "bidirectional"))
    )
    (net (code "72") (name "unconnected-(MOT2-PadVM)") (class "Default")
      (node (ref "MOT2") (pin "VM") (pinfunction "VM_VM") (pintype "bidirectional"))
    )
    (net (code "73") (name "unconnected-(MOT3-PadVM)") (class "Default")
      (node (ref "MOT3") (pin "VM") (pinfunction "VM_VM") (pintype "bidirectional"))
    )
    (net (code "74") (name "unconnected-(U$2-0{slash}RX1{slash}T-Pad0)") (class "Default")
      (node (ref "U$2") (pin "0") (pinfunction "0/RX1/T_0") (pintype "bidirectional"))
    )
    (net (code "75") (name "unconnected-(U$2-1{slash}TX1{slash}T-Pad1)") (class "Default")
      (node (ref "U$2") (pin "1") (pinfunction "1/TX1/T_1") (pintype "bidirectional"))
    )
    (net (code "76") (name "unconnected-(U$2-A14{slash}DAC-PadRESET{slash}DAC)") (class "Default")
      (node (ref "U$2") (pin "RESET/DAC") (pinfunction "A14/DAC_RESET/DAC") (pintype "bidirectional"))
    )
    (net (code "77") (name "unconnected-(U$2-Pad24)") (class "Default")
      (node (ref "U$2") (pin "24") (pinfunction "24_24") (pintype "bidirectional"))
    )
    (net (code "78") (name "unconnected-(U$2-PadPGM)") (class "Default")
      (node (ref "U$2") (pin "PGM") (pinfunction "PGM_PGM") (pintype "bidirectional"))
    )
  )
)
